# mainboard_v3.net
KiCad netlist of a schematic drawn in EAGLE
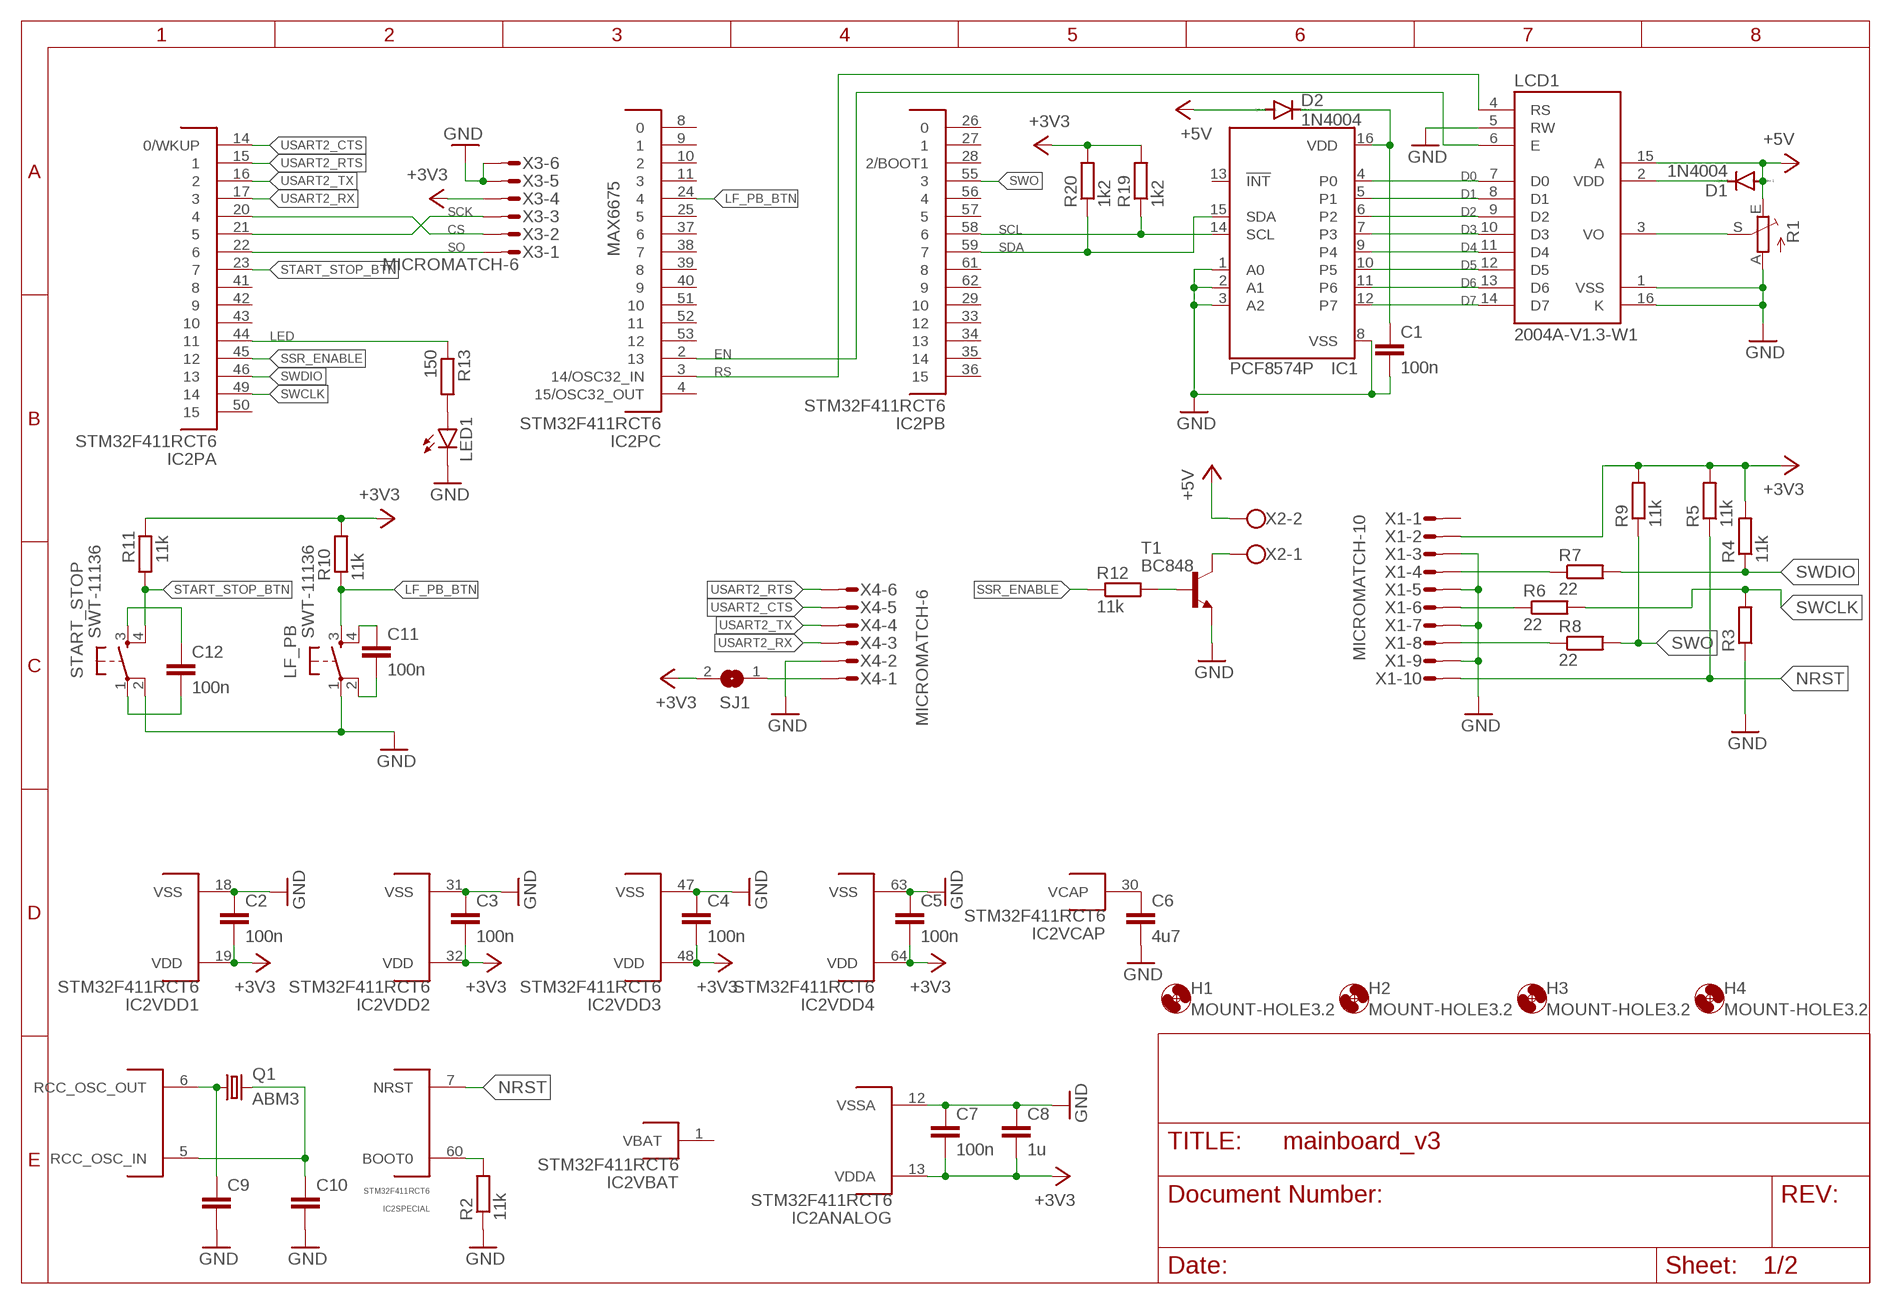
[diagram p0: schematic, sheet 1]
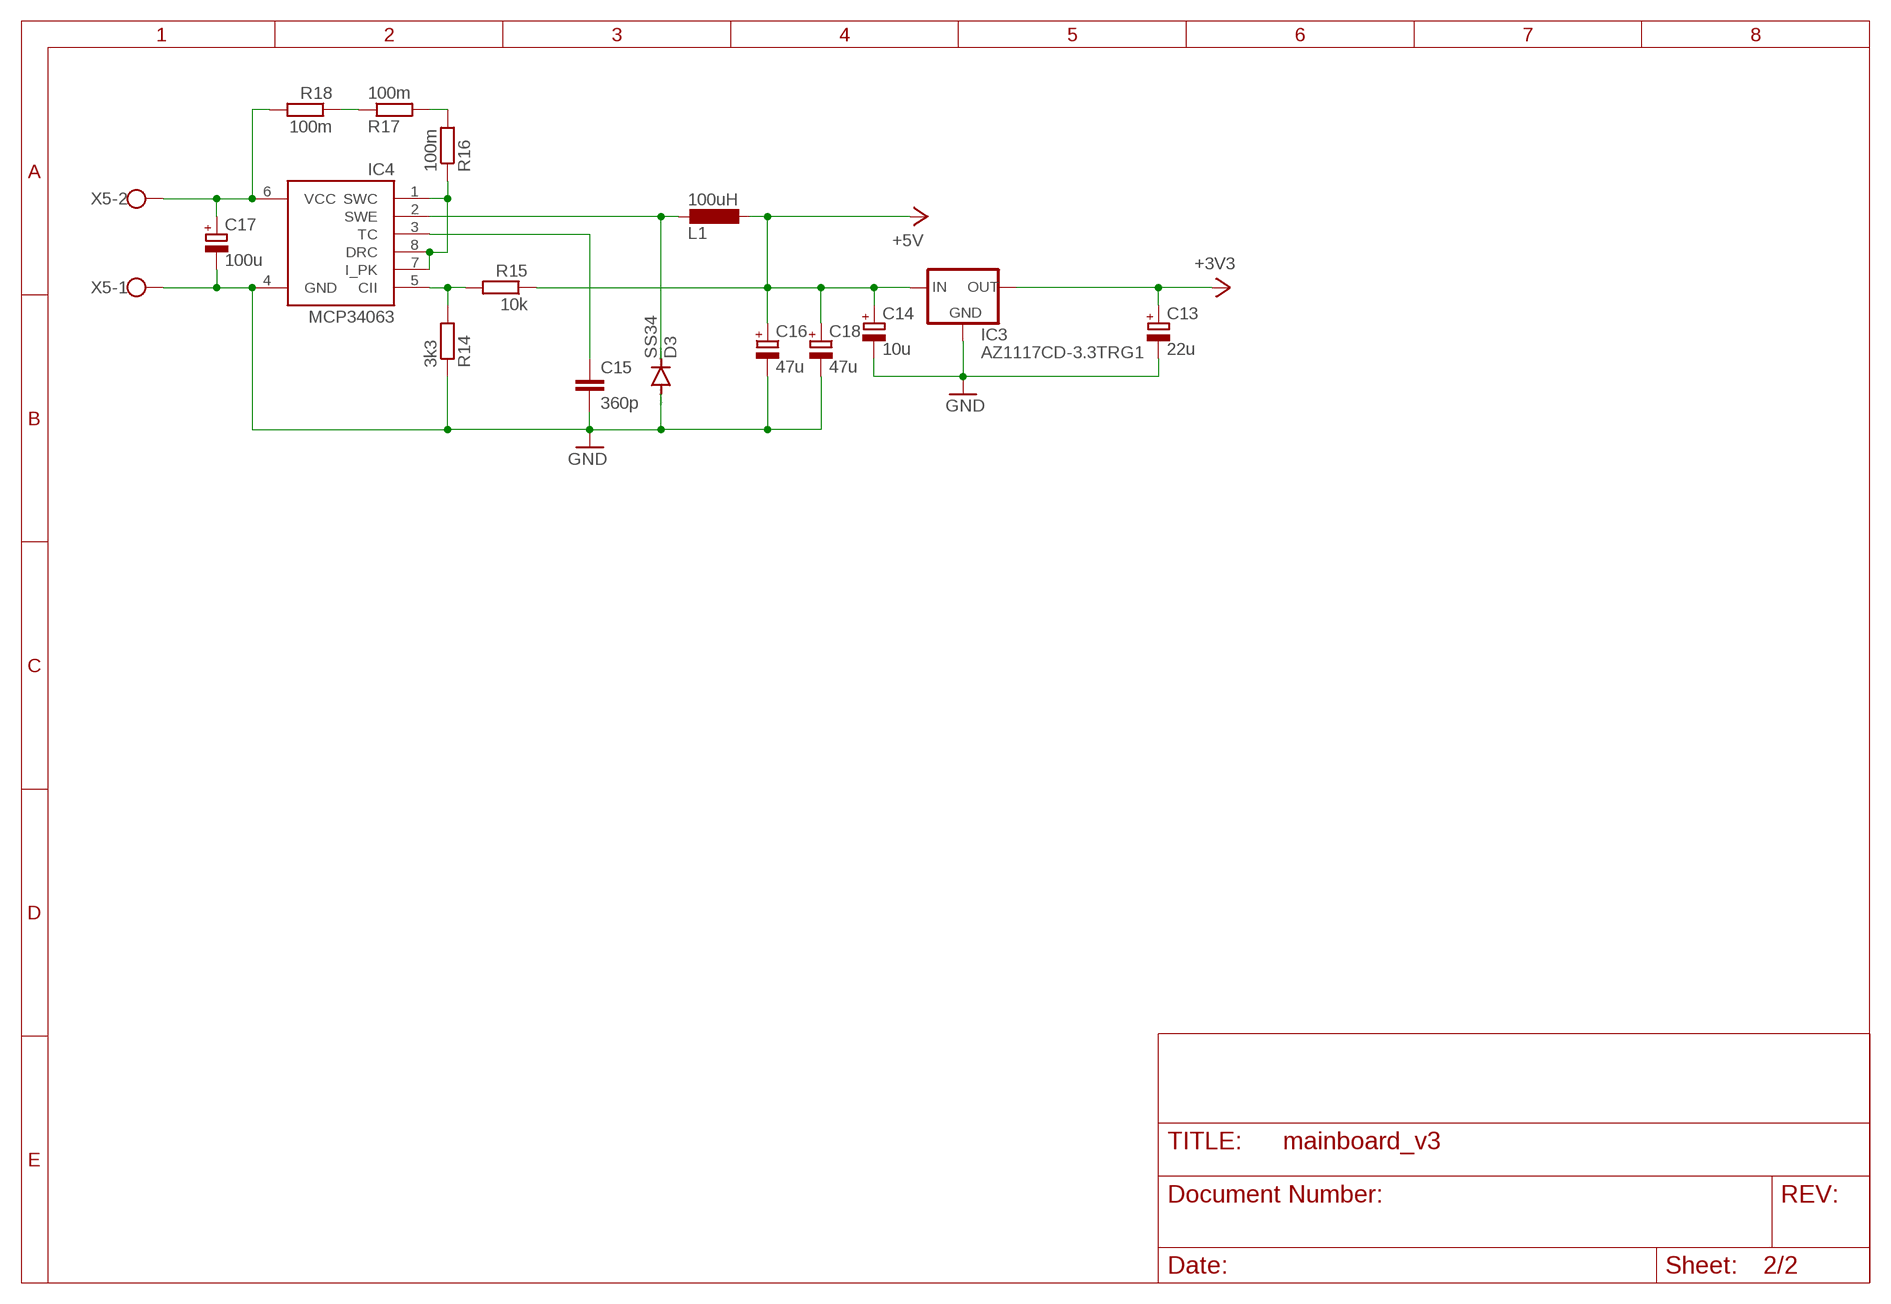
[diagram p1: schematic, sheet 2]

(export (version "E")
  (design (tool "Eeschema 10.0.6"))
  (components
    (comp (ref "C1")
      (value "100n")
      (footprint "eagle-import:C0805")
      (libsource (lib "eagle-import") (part "C-EUC0805"))
    )
    (comp (ref "C2")
      (value "100n")
      (footprint "eagle-import:C0805")
      (libsource (lib "eagle-import") (part "C-EUC0805"))
    )
    (comp (ref "C3")
      (value "100n")
      (footprint "eagle-import:C0805")
      (libsource (lib "eagle-import") (part "C-EUC0805"))
    )
    (comp (ref "C4")
      (value "100n")
      (footprint "eagle-import:C0805")
      (libsource (lib "eagle-import") (part "C-EUC0805"))
    )
    (comp (ref "C5")
      (value "100n")
      (footprint "eagle-import:C0805")
      (libsource (lib "eagle-import") (part "C-EUC0805"))
    )
    (comp (ref "C6")
      (value "4u7")
      (footprint "eagle-import:C0805")
      (libsource (lib "eagle-import") (part "C-EUC0805"))
    )
    (comp (ref "C7")
      (value "100n")
      (footprint "eagle-import:C0805")
      (libsource (lib "eagle-import") (part "C-EUC0805"))
    )
    (comp (ref "C8")
      (value "1u")
      (footprint "eagle-import:C0805")
      (libsource (lib "eagle-import") (part "C-EUC0805"))
    )
    (comp (ref "C9")
      (value "C-EUC0805")
      (footprint "eagle-import:C0805")
      (libsource (lib "eagle-import") (part "C-EUC0805"))
    )
    (comp (ref "C10")
      (value "C-EUC0805")
      (footprint "eagle-import:C0805")
      (libsource (lib "eagle-import") (part "C-EUC0805"))
    )
    (comp (ref "C11")
      (value "100n")
      (footprint "eagle-import:C0805")
      (libsource (lib "eagle-import") (part "C-EUC0805"))
    )
    (comp (ref "C12")
      (value "100n")
      (footprint "eagle-import:C0805")
      (libsource (lib "eagle-import") (part "C-EUC0805"))
    )
    (comp (ref "D1")
      (value "1N4004")
      (footprint "eagle-import:DO41-10")
      (libsource (lib "eagle-import") (part "1N4004"))
    )
    (comp (ref "D2")
      (value "1N4004")
      (footprint "eagle-import:DO41-10")
      (libsource (lib "eagle-import") (part "1N4004"))
    )
    (comp (ref "H1")
      (value "MOUNT-HOLE3.2")
      (footprint "eagle-import:3,2")
      (libsource (lib "eagle-import") (part "MOUNT-HOLE3.2"))
    )
    (comp (ref "H2")
      (value "MOUNT-HOLE3.2")
      (footprint "eagle-import:3,2")
      (libsource (lib "eagle-import") (part "MOUNT-HOLE3.2"))
    )
    (comp (ref "H3")
      (value "MOUNT-HOLE3.2")
      (footprint "eagle-import:3,2")
      (libsource (lib "eagle-import") (part "MOUNT-HOLE3.2"))
    )
    (comp (ref "H4")
      (value "MOUNT-HOLE3.2")
      (footprint "eagle-import:3,2")
      (libsource (lib "eagle-import") (part "MOUNT-HOLE3.2"))
    )
    (comp (ref "IC1")
      (value "PCF8574P")
      (footprint "eagle-import:DIL16")
      (fields (field (name "MPN") "PCF8574PN"))
      (libsource (lib "eagle-import") (part "PCF8574P"))
    )
    (comp (ref "IC2")
      (value "STM32F411RCT6")
      (footprint "eagle-import:QFP50P1200X1200X160-64N")
      (libsource (lib "eagle-import") (part "STM32F411RCT6"))
    )
    (comp (ref "LCD1")
      (value "2004A-V1.3-W1")
      (footprint "eagle-import:2004A-V1.3-W1")
      (libsource (lib "eagle-import") (part "2004A-V1.3-W1"))
    )
    (comp (ref "LED1")
      (value "LED5MM")
      (footprint "eagle-import:LED5MM")
      (libsource (lib "eagle-import") (part "LED5MM"))
    )
    (comp (ref "LF_PB")
      (value "SWT-11136")
      (footprint "eagle-import:SWT-11136")
      (libsource (lib "eagle-import") (part "SWT-11136"))
    )
    (comp (ref "Q1")
      (value "ABM3")
      (footprint "eagle-import:XTALDFN500X320X130-2N")
      (libsource (lib "eagle-import") (part "ABM3"))
    )
    (comp (ref "R1")
      (value "TRIM_EU-CA9V")
      (footprint "eagle-import:CA9V")
      (libsource (lib "eagle-import") (part "TRIM_EU-CA9V"))
    )
    (comp (ref "R2")
      (value "11k")
      (footprint "eagle-import:R1206")
      (libsource (lib "eagle-import") (part "R-EU_R1206"))
    )
    (comp (ref "R3")
      (value "R-EU_R1206")
      (footprint "eagle-import:R1206")
      (libsource (lib "eagle-import") (part "R-EU_R1206"))
    )
    (comp (ref "R4")
      (value "11k")
      (footprint "eagle-import:R1206")
      (libsource (lib "eagle-import") (part "R-EU_R1206"))
    )
    (comp (ref "R5")
      (value "11k")
      (footprint "eagle-import:R1206")
      (libsource (lib "eagle-import") (part "R-EU_R1206"))
    )
    (comp (ref "R6")
      (value "22")
      (footprint "eagle-import:R0603")
      (libsource (lib "eagle-import") (part "R-EU_R0603"))
    )
    (comp (ref "R7")
      (value "22")
      (footprint "eagle-import:R0603")
      (libsource (lib "eagle-import") (part "R-EU_R0603"))
    )
    (comp (ref "R8")
      (value "22")
      (footprint "eagle-import:R0603")
      (libsource (lib "eagle-import") (part "R-EU_R0603"))
    )
    (comp (ref "R9")
      (value "11k")
      (footprint "eagle-import:R1206")
      (libsource (lib "eagle-import") (part "R-EU_R1206"))
    )
    (comp (ref "R10")
      (value "11k")
      (footprint "eagle-import:R1206")
      (libsource (lib "eagle-import") (part "R-EU_R1206"))
    )
    (comp (ref "R11")
      (value "11k")
      (footprint "eagle-import:R1206")
      (libsource (lib "eagle-import") (part "R-EU_R1206"))
    )
    (comp (ref "R12")
      (value "11k")
      (footprint "eagle-import:R1206")
      (libsource (lib "eagle-import") (part "R-EU_R1206"))
    )
    (comp (ref "R13")
      (value "150")
      (footprint "eagle-import:R0805")
      (libsource (lib "eagle-import") (part "R-EU_R0805"))
    )
    (comp (ref "R19")
      (value "1k2")
      (footprint "eagle-import:0207_12")
      (libsource (lib "eagle-import") (part "R-EU_0207/12"))
    )
    (comp (ref "R20")
      (value "1k2")
      (footprint "eagle-import:0207_12")
      (libsource (lib "eagle-import") (part "R-EU_0207/12"))
    )
    (comp (ref "SJ1") (value "SJ") (footprint "eagle-import:SJ") (libsource (lib "eagle-import") (part "SJ")))
    (comp (ref "START_STOP")
      (value "SWT-11136")
      (footprint "eagle-import:SWT-11136")
      (libsource (lib "eagle-import") (part "SWT-11136"))
    )
    (comp (ref "T1")
      (value "BC848")
      (footprint "eagle-import:SOT23")
      (libsource (lib "eagle-import") (part "BC848"))
    )
    (comp (ref "X1")
      (value "MICROMATCH-10")
      (footprint "eagle-import:MICROMATCH-10")
      (fields (field (name "MF") "FARNELL") (field (name "MPN") "8-215464-0"))
      (libsource (lib "eagle-import") (part "MICROMATCH-10"))
    )
    (comp (ref "X2")
      (value "W237-102")
      (footprint "eagle-import:W237-102")
      (fields (field (name "MPN") "237-102"))
      (libsource (lib "eagle-import") (part "W237-102"))
    )
    (comp (ref "X3")
      (value "MICROMATCH-6")
      (footprint "eagle-import:MICROMATCH-6")
      (fields (field (name "MPN") "7-215464-6"))
      (libsource (lib "eagle-import") (part "MICROMATCH-6"))
    )
    (comp (ref "X4")
      (value "MICROMATCH-6")
      (footprint "eagle-import:MICROMATCH-6")
      (fields (field (name "MPN") "7-215464-6"))
      (libsource (lib "eagle-import") (part "MICROMATCH-6"))
    )
    (comp (ref "C13")
      (value "22u")
      (footprint "eagle-import:SMC_B")
      (libsource (lib "eagle-import") (part "CPOL-EUSMCB"))
    )
    (comp (ref "C14")
      (value "10u")
      (footprint "eagle-import:SMC_A")
      (libsource (lib "eagle-import") (part "CPOL-EUSMCA"))
    )
    (comp (ref "C15")
      (value "360p")
      (footprint "eagle-import:C1206")
      (libsource (lib "eagle-import") (part "C-EUC1206"))
    )
    (comp (ref "C16")
      (value "47u")
      (footprint "eagle-import:SMC_D")
      (libsource (lib "eagle-import") (part "CPOL-EUSMCD"))
    )
    (comp (ref "C17")
      (value "100u")
      (footprint "eagle-import:E5-8,5")
      (libsource (lib "eagle-import") (part "CPOL-EUE5-8.5"))
    )
    (comp (ref "C18")
      (value "47u")
      (footprint "eagle-import:SMC_D")
      (libsource (lib "eagle-import") (part "CPOL-EUSMCD"))
    )
    (comp (ref "D3")
      (value "SS34")
      (footprint "eagle-import:SMB")
      (libsource (lib "eagle-import") (part "DIODE-SMB"))
    )
    (comp (ref "IC3")
      (value "AZ1117CD-3.3TRG1")
      (footprint "eagle-import:TO228P1014X240-3N")
      (libsource (lib "eagle-import") (part "AZ1117CD-3.3TRG1"))
    )
    (comp (ref "IC4")
      (value "MCP34063")
      (footprint "eagle-import:SOIC127P600X175-8N")
      (libsource (lib "eagle-import") (part "MCP34063"))
    )
    (comp (ref "L1")
      (value "100uH")
      (footprint "eagle-import:INDM7770X500N")
      (libsource (lib "eagle-import") (part "SOMETHING_100UH"))
    )
    (comp (ref "R14")
      (value "3k3")
      (footprint "eagle-import:R1206")
      (libsource (lib "eagle-import") (part "R-EU_R1206"))
    )
    (comp (ref "R15")
      (value "10k")
      (footprint "eagle-import:R1206")
      (libsource (lib "eagle-import") (part "R-EU_R1206"))
    )
    (comp (ref "R16")
      (value "100m")
      (footprint "eagle-import:0309_12")
      (libsource (lib "eagle-import") (part "R-EU_0309/12"))
    )
    (comp (ref "R17")
      (value "100m")
      (footprint "eagle-import:0309_12")
      (libsource (lib "eagle-import") (part "R-EU_0309/12"))
    )
    (comp (ref "R18")
      (value "100m")
      (footprint "eagle-import:0309_12")
      (libsource (lib "eagle-import") (part "R-EU_0309/12"))
    )
    (comp (ref "X5")
      (value "W237-102")
      (footprint "eagle-import:W237-102")
      (fields (field (name "MPN") "237-102"))
      (libsource (lib "eagle-import") (part "W237-102"))
    )
  )
  (nets
    (net (code "1") (name "+3V3") (class "Default")
      (node (ref "C13") (pin "+") (pinfunction "+_+") (pintype "passive"))
      (node (ref "C2") (pin "2") (pinfunction "2_2") (pintype "passive"))
      (node (ref "C3") (pin "2") (pinfunction "2_2") (pintype "passive"))
      (node (ref "C4") (pin "2") (pinfunction "2_2") (pintype "passive"))
      (node (ref "C5") (pin "2") (pinfunction "2_2") (pintype "passive"))
      (node (ref "C7") (pin "2") (pinfunction "2_2") (pintype "passive"))
      (node (ref "C8") (pin "2") (pinfunction "2_2") (pintype "passive"))
      (node (ref "IC2") (pin "13") (pinfunction "VDDA_13") (pintype "power_in"))
      (node (ref "IC2") (pin "19") (pinfunction "VDD_19") (pintype "power_in"))
      (node (ref "IC2") (pin "32") (pinfunction "VDD_32") (pintype "power_in"))
      (node (ref "IC2") (pin "48") (pinfunction "VDD_48") (pintype "power_in"))
      (node (ref "IC2") (pin "64") (pinfunction "VDD_64") (pintype "power_in"))
      (node (ref "IC3") (pin "3") (pinfunction "OUT_3") (pintype "passive"))
      (node (ref "R10") (pin "2") (pinfunction "2_2") (pintype "passive"))
      (node (ref "R11") (pin "2") (pinfunction "2_2") (pintype "passive"))
      (node (ref "R19") (pin "2") (pinfunction "2_2") (pintype "passive"))
      (node (ref "R20") (pin "2") (pinfunction "2_2") (pintype "passive"))
      (node (ref "R4") (pin "2") (pinfunction "2_2") (pintype "passive"))
      (node (ref "R5") (pin "2") (pinfunction "2_2") (pintype "passive"))
      (node (ref "R9") (pin "2") (pinfunction "2_2") (pintype "passive"))
      (node (ref "SJ1") (pin "2") (pinfunction "2_2") (pintype "passive"))
      (node (ref "X1") (pin "2") (pinfunction "S_2") (pintype "passive"))
      (node (ref "X3") (pin "4") (pinfunction "S_4") (pintype "passive"))
    )
    (net (code "2") (name "+5V") (class "Default")
      (node (ref "C14") (pin "+") (pinfunction "+_+") (pintype "passive"))
      (node (ref "C16") (pin "+") (pinfunction "+_+") (pintype "passive"))
      (node (ref "C18") (pin "+") (pinfunction "+_+") (pintype "passive"))
      (node (ref "D1") (pin "A") (pinfunction "A_A") (pintype "passive"))
      (node (ref "D2") (pin "A") (pinfunction "A_A") (pintype "passive"))
      (node (ref "IC3") (pin "2") (pinfunction "IN_2") (pintype "input"))
      (node (ref "L1") (pin "1") (pinfunction "1_1") (pintype "passive"))
      (node (ref "LCD1") (pin "15") (pinfunction "A_15") (pintype "power_in"))
      (node (ref "R1") (pin "E") (pinfunction "E_E") (pintype "passive"))
      (node (ref "R15") (pin "1") (pinfunction "1_1") (pintype "passive"))
      (node (ref "X2") (pin "2") (pinfunction "KL_2") (pintype "passive"))
    )
    (net (code "3") (name "CS") (class "Default")
      (node (ref "IC2") (pin "20") (pinfunction "4_20") (pintype "bidirectional"))
      (node (ref "X3") (pin "2") (pinfunction "S_2") (pintype "passive"))
    )
    (net (code "4") (name "D0") (class "Default")
      (node (ref "IC1") (pin "4") (pinfunction "P0_4") (pintype "bidirectional"))
      (node (ref "LCD1") (pin "7") (pinfunction "D0_7") (pintype "bidirectional"))
    )
    (net (code "5") (name "D1") (class "Default")
      (node (ref "IC1") (pin "5") (pinfunction "P1_5") (pintype "bidirectional"))
      (node (ref "LCD1") (pin "8") (pinfunction "D1_8") (pintype "bidirectional"))
    )
    (net (code "6") (name "D2") (class "Default")
      (node (ref "IC1") (pin "6") (pinfunction "P2_6") (pintype "bidirectional"))
      (node (ref "LCD1") (pin "9") (pinfunction "D2_9") (pintype "bidirectional"))
    )
    (net (code "7") (name "D3") (class "Default")
      (node (ref "IC1") (pin "7") (pinfunction "P3_7") (pintype "bidirectional"))
      (node (ref "LCD1") (pin "10") (pinfunction "D3_10") (pintype "bidirectional"))
    )
    (net (code "8") (name "D4") (class "Default")
      (node (ref "IC1") (pin "9") (pinfunction "P4_9") (pintype "bidirectional"))
      (node (ref "LCD1") (pin "11") (pinfunction "D4_11") (pintype "bidirectional"))
    )
    (net (code "9") (name "D5") (class "Default")
      (node (ref "IC1") (pin "10") (pinfunction "P5_10") (pintype "bidirectional"))
      (node (ref "LCD1") (pin "12") (pinfunction "D5_12") (pintype "bidirectional"))
    )
    (net (code "10") (name "D6") (class "Default")
      (node (ref "IC1") (pin "11") (pinfunction "P6_11") (pintype "bidirectional"))
      (node (ref "LCD1") (pin "13") (pinfunction "D6_13") (pintype "bidirectional"))
    )
    (net (code "11") (name "D7") (class "Default")
      (node (ref "IC1") (pin "12") (pinfunction "P7_12") (pintype "bidirectional"))
      (node (ref "LCD1") (pin "14") (pinfunction "D7_14") (pintype "bidirectional"))
    )
    (net (code "12") (name "EN") (class "Default")
      (node (ref "IC2") (pin "2") (pinfunction "13_2") (pintype "bidirectional"))
      (node (ref "LCD1") (pin "6") (pinfunction "E_6") (pintype "input"))
    )
    (net (code "13") (name "GND") (class "Default")
      (node (ref "C1") (pin "2") (pinfunction "2_2") (pintype "passive"))
      (node (ref "C10") (pin "2") (pinfunction "2_2") (pintype "passive"))
      (node (ref "C13") (pin "-") (pinfunction "-_-") (pintype "passive"))
      (node (ref "C14") (pin "-") (pinfunction "-_-") (pintype "passive"))
      (node (ref "C15") (pin "2") (pinfunction "2_2") (pintype "passive"))
      (node (ref "C16") (pin "-") (pinfunction "-_-") (pintype "passive"))
      (node (ref "C17") (pin "-") (pinfunction "-_-") (pintype "passive"))
      (node (ref "C18") (pin "-") (pinfunction "-_-") (pintype "passive"))
      (node (ref "C2") (pin "1") (pinfunction "1_1") (pintype "passive"))
      (node (ref "C3") (pin "1") (pinfunction "1_1") (pintype "passive"))
      (node (ref "C4") (pin "1") (pinfunction "1_1") (pintype "passive"))
      (node (ref "C5") (pin "1") (pinfunction "1_1") (pintype "passive"))
      (node (ref "C6") (pin "2") (pinfunction "2_2") (pintype "passive"))
      (node (ref "C7") (pin "1") (pinfunction "1_1") (pintype "passive"))
      (node (ref "C8") (pin "1") (pinfunction "1_1") (pintype "passive"))
      (node (ref "C9") (pin "2") (pinfunction "2_2") (pintype "passive"))
      (node (ref "D3") (pin "A") (pinfunction "A_A") (pintype "passive"))
      (node (ref "IC1") (pin "1") (pinfunction "A0_1") (pintype "input"))
      (node (ref "IC1") (pin "2") (pinfunction "A1_2") (pintype "input"))
      (node (ref "IC1") (pin "3") (pinfunction "A2_3") (pintype "input"))
      (node (ref "IC1") (pin "8") (pinfunction "VSS_8") (pintype "power_in"))
      (node (ref "IC2") (pin "12") (pinfunction "VSSA_12") (pintype "power_in"))
      (node (ref "IC2") (pin "18") (pinfunction "VSS_18") (pintype "power_in"))
      (node (ref "IC2") (pin "31") (pinfunction "VSS_31") (pintype "power_in"))
      (node (ref "IC2") (pin "47") (pinfunction "VSS_47") (pintype "power_in"))
      (node (ref "IC2") (pin "63") (pinfunction "VSS_63") (pintype "power_in"))
      (node (ref "IC3") (pin "1") (pinfunction "GND_1") (pintype "input"))
      (node (ref "IC4") (pin "4") (pinfunction "GND_4") (pintype "power_in"))
      (node (ref "LCD1") (pin "1") (pinfunction "VSS_1") (pintype "power_in"))
      (node (ref "LCD1") (pin "16") (pinfunction "K_16") (pintype "power_in"))
      (node (ref "LCD1") (pin "5") (pinfunction "RW_5") (pintype "input"))
      (node (ref "LED1") (pin "K") (pinfunction "C_K") (pintype "passive"))
      (node (ref "LF_PB") (pin "1") (pinfunction "P_1") (pintype "passive"))
      (node (ref "R1") (pin "A") (pinfunction "A_A") (pintype "passive"))
      (node (ref "R14") (pin "1") (pinfunction "1_1") (pintype "passive"))
      (node (ref "R2") (pin "1") (pinfunction "1_1") (pintype "passive"))
      (node (ref "R3") (pin "1") (pinfunction "1_1") (pintype "passive"))
      (node (ref "START_STOP") (pin "2") (pinfunction "P1_2") (pintype "passive"))
      (node (ref "T1") (pin "2") (pinfunction "E_2") (pintype "passive"))
      (node (ref "X1") (pin "3") (pinfunction "S_3") (pintype "passive"))
      (node (ref "X1") (pin "5") (pinfunction "S_5") (pintype "passive"))
      (node (ref "X1") (pin "7") (pinfunction "S_7") (pintype "passive"))
      (node (ref "X1") (pin "9") (pinfunction "S_9") (pintype "passive"))
      (node (ref "X3") (pin "5") (pinfunction "S_5") (pintype "passive"))
      (node (ref "X3") (pin "6") (pinfunction "S_6") (pintype "passive"))
      (node (ref "X4") (pin "2") (pinfunction "S_2") (pintype "passive"))
      (node (ref "X5") (pin "1") (pinfunction "KL_1") (pintype "passive"))
    )
    (net (code "14") (name "LED") (class "Default")
      (node (ref "IC2") (pin "44") (pinfunction "11_44") (pintype "bidirectional"))
      (node (ref "R13") (pin "1") (pinfunction "1_1") (pintype "passive"))
    )
    (net (code "15") (name "LF_PB_BTN") (class "Default")
      (node (ref "IC2") (pin "24") (pinfunction "4_24") (pintype "bidirectional"))
      (node (ref "LF_PB") (pin "3") (pinfunction "S_3") (pintype "passive"))
      (node (ref "R10") (pin "1") (pinfunction "1_1") (pintype "passive"))
    )
    (net (code "16") (name "NRST") (class "Default")
      (node (ref "IC2") (pin "7") (pinfunction "NRST_7") (pintype "bidirectional"))
      (node (ref "R5") (pin "1") (pinfunction "1_1") (pintype "passive"))
      (node (ref "X1") (pin "10") (pinfunction "S_10") (pintype "passive"))
    )
    (net (code "17") (name "Net-(IC1-VDD)") (class "Default")
      (node (ref "C1") (pin "1") (pinfunction "1_1") (pintype "passive"))
      (node (ref "D2") (pin "C") (pinfunction "C_C") (pintype "passive"))
      (node (ref "IC1") (pin "16") (pinfunction "VDD_16") (pintype "power_in"))
    )
    (net (code "18") (name "Net-(IC2F-BOOT0)") (class "Default")
      (node (ref "IC2") (pin "60") (pinfunction "BOOT0_60") (pintype "bidirectional"))
      (node (ref "R2") (pin "2") (pinfunction "2_2") (pintype "passive"))
    )
    (net (code "19") (name "Net-(IC2F-RCC_OSC_IN)") (class "Default")
      (node (ref "C10") (pin "1") (pinfunction "1_1") (pintype "passive"))
      (node (ref "IC2") (pin "5") (pinfunction "RCC_OSC_IN_5") (pintype "bidirectional"))
      (node (ref "Q1") (pin "2") (pinfunction "2_2") (pintype "passive"))
    )
    (net (code "20") (name "Net-(IC2F-RCC_OSC_OUT)") (class "Default")
      (node (ref "C9") (pin "1") (pinfunction "1_1") (pintype "passive"))
      (node (ref "IC2") (pin "6") (pinfunction "RCC_OSC_OUT_6") (pintype "bidirectional"))
      (node (ref "Q1") (pin "1") (pinfunction "1_1") (pintype "passive"))
    )
    (net (code "21") (name "Net-(IC2H-VCAP)") (class "Default")
      (node (ref "C6") (pin "1") (pinfunction "1_1") (pintype "passive"))
      (node (ref "IC2") (pin "30") (pinfunction "VCAP_30") (pintype "passive"))
    )
    (net (code "22") (name "Net-(IC4-CII)") (class "Default")
      (node (ref "IC4") (pin "5") (pinfunction "CII_5") (pintype "bidirectional"))
      (node (ref "R14") (pin "2") (pinfunction "2_2") (pintype "passive"))
      (node (ref "R15") (pin "2") (pinfunction "2_2") (pintype "passive"))
    )
    (net (code "23") (name "Net-(IC4-DRC)") (class "Default")
      (node (ref "IC4") (pin "1") (pinfunction "SWC_1") (pintype "bidirectional"))
      (node (ref "IC4") (pin "7") (pinfunction "I_PK_7") (pintype "bidirectional"))
      (node (ref "IC4") (pin "8") (pinfunction "DRC_8") (pintype "bidirectional"))
      (node (ref "R16") (pin "1") (pinfunction "1_1") (pintype "passive"))
    )
    (net (code "24") (name "Net-(IC4-SWE)") (class "Default")
      (node (ref "D3") (pin "C") (pinfunction "C_C") (pintype "passive"))
      (node (ref "IC4") (pin "2") (pinfunction "SWE_2") (pintype "bidirectional"))
      (node (ref "L1") (pin "2") (pinfunction "2_2") (pintype "passive"))
    )
    (net (code "25") (name "Net-(IC4-TC)") (class "Default")
      (node (ref "C15") (pin "1") (pinfunction "1_1") (pintype "passive"))
      (node (ref "IC4") (pin "3") (pinfunction "TC_3") (pintype "bidirectional"))
    )
    (net (code "26") (name "Net-(IC4-VCC)") (class "Default")
      (node (ref "C17") (pin "+") (pinfunction "+_+") (pintype "passive"))
      (node (ref "IC4") (pin "6") (pinfunction "VCC_6") (pintype "power_in"))
      (node (ref "R18") (pin "2") (pinfunction "2_2") (pintype "passive"))
      (node (ref "X5") (pin "2") (pinfunction "KL_2") (pintype "passive"))
    )
    (net (code "27") (name "Net-(LCD1-VDD)") (class "Default")
      (node (ref "D1") (pin "C") (pinfunction "C_C") (pintype "passive"))
      (node (ref "LCD1") (pin "2") (pinfunction "VDD_2") (pintype "power_in"))
    )
    (net (code "28") (name "Net-(LCD1-VO)") (class "Default")
      (node (ref "LCD1") (pin "3") (pinfunction "VO_3") (pintype "power_in"))
      (node (ref "R1") (pin "S") (pinfunction "S_S") (pintype "passive"))
    )
    (net (code "29") (name "Net-(LED1-PadA)") (class "Default")
      (node (ref "LED1") (pin "A") (pinfunction "A_A") (pintype "passive"))
      (node (ref "R13") (pin "2") (pinfunction "2_2") (pintype "passive"))
    )
    (net (code "30") (name "Net-(LF_PB-P1)") (class "Default")
      (node (ref "C11") (pin "2") (pinfunction "2_2") (pintype "passive"))
      (node (ref "LF_PB") (pin "2") (pinfunction "P1_2") (pintype "passive"))
    )
    (net (code "31") (name "Net-(LF_PB-S1)") (class "Default")
      (node (ref "C11") (pin "1") (pinfunction "1_1") (pintype "passive"))
      (node (ref "LF_PB") (pin "4") (pinfunction "S1_4") (pintype "passive"))
    )
    (net (code "32") (name "Net-(R16-Pad2)") (class "Default")
      (node (ref "R16") (pin "2") (pinfunction "2_2") (pintype "passive"))
      (node (ref "R17") (pin "2") (pinfunction "2_2") (pintype "passive"))
    )
    (net (code "33") (name "Net-(R17-Pad1)") (class "Default")
      (node (ref "R17") (pin "1") (pinfunction "1_1") (pintype "passive"))
      (node (ref "R18") (pin "1") (pinfunction "1_1") (pintype "passive"))
    )
    (net (code "34") (name "Net-(START_STOP-P)") (class "Default")
      (node (ref "C12") (pin "2") (pinfunction "2_2") (pintype "passive"))
      (node (ref "START_STOP") (pin "1") (pinfunction "P_1") (pintype "passive"))
    )
    (net (code "35") (name "Net-(START_STOP-S)") (class "Default")
      (node (ref "C12") (pin "1") (pinfunction "1_1") (pintype "passive"))
      (node (ref "START_STOP") (pin "3") (pinfunction "S_3") (pintype "passive"))
    )
    (net (code "36") (name "Net-(T1-B)") (class "Default")
      (node (ref "R12") (pin "2") (pinfunction "2_2") (pintype "passive"))
      (node (ref "T1") (pin "1") (pinfunction "B_1") (pintype "passive"))
    )
    (net (code "37") (name "Net-(T1-C)") (class "Default")
      (node (ref "T1") (pin "3") (pinfunction "C_3") (pintype "passive"))
      (node (ref "X2") (pin "1") (pinfunction "KL_1") (pintype "passive"))
    )
    (net (code "38") (name "Net-(X1E-S)") (class "Default")
      (node (ref "R7") (pin "1") (pinfunction "1_1") (pintype "passive"))
      (node (ref "X1") (pin "4") (pinfunction "S_4") (pintype "passive"))
    )
    (net (code "39") (name "Net-(X1G-S)") (class "Default")
      (node (ref "R6") (pin "1") (pinfunction "1_1") (pintype "passive"))
      (node (ref "X1") (pin "6") (pinfunction "S_6") (pintype "passive"))
    )
    (net (code "40") (name "Net-(X1I-S)") (class "Default")
      (node (ref "R8") (pin "1") (pinfunction "1_1") (pintype "passive"))
      (node (ref "X1") (pin "8") (pinfunction "S_8") (pintype "passive"))
    )
    (net (code "41") (name "Net-(X4A-S)") (class "Default")
      (node (ref "SJ1") (pin "1") (pinfunction "1_1") (pintype "passive"))
      (node (ref "X4") (pin "1") (pinfunction "S_1") (pintype "passive"))
    )
    (net (code "42") (name "RS") (class "Default")
      (node (ref "IC2") (pin "3") (pinfunction "14/OSC32_IN_3") (pintype "bidirectional"))
      (node (ref "LCD1") (pin "4") (pinfunction "RS_4") (pintype "input"))
    )
    (net (code "43") (name "SCK") (class "Default")
      (node (ref "IC2") (pin "21") (pinfunction "5_21") (pintype "bidirectional"))
      (node (ref "X3") (pin "3") (pinfunction "S_3") (pintype "passive"))
    )
    (net (code "44") (name "SCL") (class "Default")
      (node (ref "IC1") (pin "14") (pinfunction "SCL_14") (pintype "input"))
      (node (ref "IC2") (pin "58") (pinfunction "6_58") (pintype "bidirectional"))
      (node (ref "R19") (pin "1") (pinfunction "1_1") (pintype "passive"))
    )
    (net (code "45") (name "SDA") (class "Default")
      (node (ref "IC1") (pin "15") (pinfunction "SDA_15") (pintype "bidirectional"))
      (node (ref "IC2") (pin "59") (pinfunction "7_59") (pintype "bidirectional"))
      (node (ref "R20") (pin "1") (pinfunction "1_1") (pintype "passive"))
    )
    (net (code "46") (name "SO") (class "Default")
      (node (ref "IC2") (pin "22") (pinfunction "6_22") (pintype "bidirectional"))
      (node (ref "X3") (pin "1") (pinfunction "S_1") (pintype "passive"))
    )
    (net (code "47") (name "SSR_ENABLE") (class "Default")
      (node (ref "IC2") (pin "45") (pinfunction "12_45") (pintype "bidirectional"))
      (node (ref "R12") (pin "1") (pinfunction "1_1") (pintype "passive"))
    )
    (net (code "48") (name "START_STOP_BTN") (class "Default")
      (node (ref "IC2") (pin "23") (pinfunction "7_23") (pintype "bidirectional"))
      (node (ref "R11") (pin "1") (pinfunction "1_1") (pintype "passive"))
      (node (ref "START_STOP") (pin "4") (pinfunction "S1_4") (pintype "passive"))
    )
    (net (code "49") (name "SWCLK") (class "Default")
      (node (ref "IC2") (pin "49") (pinfunction "14_49") (pintype "bidirectional"))
      (node (ref "R3") (pin "2") (pinfunction "2_2") (pintype "passive"))
      (node (ref "R6") (pin "2") (pinfunction "2_2") (pintype "passive"))
    )
    (net (code "50") (name "SWDIO") (class "Default")
      (node (ref "IC2") (pin "46") (pinfunction "13_46") (pintype "bidirectional"))
      (node (ref "R4") (pin "1") (pinfunction "1_1") (pintype "passive"))
      (node (ref "R7") (pin "2") (pinfunction "2_2") (pintype "passive"))
    )
    (net (code "51") (name "SWO") (class "Default")
      (node (ref "IC2") (pin "55") (pinfunction "3_55") (pintype "bidirectional"))
      (node (ref "R8") (pin "2") (pinfunction "2_2") (pintype "passive"))
      (node (ref "R9") (pin "1") (pinfunction "1_1") (pintype "passive"))
    )
    (net (code "52") (name "USART2_CTS") (class "Default")
      (node (ref "IC2") (pin "14") (pinfunction "0/WKUP_14") (pintype "bidirectional"))
      (node (ref "X4") (pin "5") (pinfunction "S_5") (pintype "passive"))
    )
    (net (code "53") (name "USART2_RTS") (class "Default")
      (node (ref "IC2") (pin "15") (pinfunction "1_15") (pintype "bidirectional"))
      (node (ref "X4") (pin "6") (pinfunction "S_6") (pintype "passive"))
    )
    (net (code "54") (name "USART2_RX") (class "Default")
      (node (ref "IC2") (pin "17") (pinfunction "3_17") (pintype "bidirectional"))
      (node (ref "X4") (pin "3") (pinfunction "S_3") (pintype "passive"))
    )
    (net (code "55") (name "USART2_TX") (class "Default")
      (node (ref "IC2") (pin "16") (pinfunction "2_16") (pintype "bidirectional"))
      (node (ref "X4") (pin "4") (pinfunction "S_4") (pintype "passive"))
    )
    (net (code "56") (name "VBAT") (class "Default")
      (node (ref "IC2") (pin "1") (pinfunction "VBAT_1") (pintype "power_in"))
    )
    (net (code "57") (name "unconnected-(IC1-~{INT}-Pad13)") (class "Default")
      (node (ref "IC1") (pin "13") (pinfunction "~{INT}_13") (pintype "output"))
    )
    (net (code "58") (name "unconnected-(IC2B-8-Pad41)") (class "Default")
      (node (ref "IC2") (pin "41") (pinfunction "8_41") (pintype "bidirectional"))
    )
    (net (code "59") (name "unconnected-(IC2B-9-Pad42)") (class "Default")
      (node (ref "IC2") (pin "42") (pinfunction "9_42") (pintype "bidirectional"))
    )
    (net (code "60") (name "unconnected-(IC2B-10-Pad43)") (class "Default")
      (node (ref "IC2") (pin "43") (pinfunction "10_43") (pintype "bidirectional"))
    )
    (net (code "61") (name "unconnected-(IC2B-15-Pad50)") (class "Default")
      (node (ref "IC2") (pin "50") (pinfunction "15_50") (pintype "bidirectional"))
    )
    (net (code "62") (name "unconnected-(IC2C-0-Pad26)") (class "Default")
      (node (ref "IC2") (pin "26") (pinfunction "0_26") (pintype "bidirectional"))
    )
    (net (code "63") (name "unconnected-(IC2C-1-Pad27)") (class "Default")
      (node (ref "IC2") (pin "27") (pinfunction "1_27") (pintype "bidirectional"))
    )
    (net (code "64") (name "unconnected-(IC2C-2{slash}BOOT1-Pad28)") (class "Default")
      (node (ref "IC2") (pin "28") (pinfunction "2/BOOT1_28") (pintype "bidirectional"))
    )
    (net (code "65") (name "unconnected-(IC2C-4-Pad56)") (class "Default")
      (node (ref "IC2") (pin "56") (pinfunction "4_56") (pintype "bidirectional"))
    )
    (net (code "66") (name "unconnected-(IC2C-5-Pad57)") (class "Default")
      (node (ref "IC2") (pin "57") (pinfunction "5_57") (pintype "bidirectional"))
    )
    (net (code "67") (name "unconnected-(IC2C-8-Pad61)") (class "Default")
      (node (ref "IC2") (pin "61") (pinfunction "8_61") (pintype "bidirectional"))
    )
    (net (code "68") (name "unconnected-(IC2C-9-Pad62)") (class "Default")
      (node (ref "IC2") (pin "62") (pinfunction "9_62") (pintype "bidirectional"))
    )
    (net (code "69") (name "unconnected-(IC2C-10-Pad29)") (class "Default")
      (node (ref "IC2") (pin "29") (pinfunction "10_29") (pintype "bidirectional"))
    )
    (net (code "70") (name "unconnected-(IC2C-12-Pad33)") (class "Default")
      (node (ref "IC2") (pin "33") (pinfunction "12_33") (pintype "bidirectional"))
    )
    (net (code "71") (name "unconnected-(IC2C-13-Pad34)") (class "Default")
      (node (ref "IC2") (pin "34") (pinfunction "13_34") (pintype "bidirectional"))
    )
    (net (code "72") (name "unconnected-(IC2C-14-Pad35)") (class "Default")
      (node (ref "IC2") (pin "35") (pinfunction "14_35") (pintype "bidirectional"))
    )
    (net (code "73") (name "unconnected-(IC2C-15-Pad36)") (class "Default")
      (node (ref "IC2") (pin "36") (pinfunction "15_36") (pintype "bidirectional"))
    )
    (net (code "74") (name "unconnected-(IC2D-0-Pad8)") (class "Default")
      (node (ref "IC2") (pin "8") (pinfunction "0_8") (pintype "bidirectional"))
    )
    (net (code "75") (name "unconnected-(IC2D-1-Pad9)") (class "Default")
      (node (ref "IC2") (pin "9") (pinfunction "1_9") (pintype "bidirectional"))
    )
    (net (code "76") (name "unconnected-(IC2D-2-Pad10)") (class "Default")
      (node (ref "IC2") (pin "10") (pinfunction "2_10") (pintype "bidirectional"))
    )
    (net (code "77") (name "unconnected-(IC2D-3-Pad11)") (class "Default")
      (node (ref "IC2") (pin "11") (pinfunction "3_11") (pintype "bidirectional"))
    )
    (net (code "78") (name "unconnected-(IC2D-5-Pad25)") (class "Default")
      (node (ref "IC2") (pin "25") (pinfunction "5_25") (pintype "bidirectional"))
    )
    (net (code "79") (name "unconnected-(IC2D-6-Pad37)") (class "Default")
      (node (ref "IC2") (pin "37") (pinfunction "6_37") (pintype "bidirectional"))
    )
    (net (code "80") (name "unconnected-(IC2D-7-Pad38)") (class "Default")
      (node (ref "IC2") (pin "38") (pinfunction "7_38") (pintype "bidirectional"))
    )
    (net (code "81") (name "unconnected-(IC2D-8-Pad39)") (class "Default")
      (node (ref "IC2") (pin "39") (pinfunction "8_39") (pintype "bidirectional"))
    )
    (net (code "82") (name "unconnected-(IC2D-9-Pad40)") (class "Default")
      (node (ref "IC2") (pin "40") (pinfunction "9_40") (pintype "bidirectional"))
    )
    (net (code "83") (name "unconnected-(IC2D-10-Pad51)") (class "Default")
      (node (ref "IC2") (pin "51") (pinfunction "10_51") (pintype "bidirectional"))
    )
    (net (code "84") (name "unconnected-(IC2D-11-Pad52)") (class "Default")
      (node (ref "IC2") (pin "52") (pinfunction "11_52") (pintype "bidirectional"))
    )
    (net (code "85") (name "unconnected-(IC2D-12-Pad53)") (class "Default")
      (node (ref "IC2") (pin "53") (pinfunction "12_53") (pintype "bidirectional"))
    )
    (net (code "86") (name "unconnected-(IC2D-15{slash}OSC32_OUT-Pad4)") (class "Default")
      (node (ref "IC2") (pin "4") (pinfunction "15/OSC32_OUT_4") (pintype "bidirectional"))
    )
    (net (code "87") (name "unconnected-(X1A-S-Pad1)") (class "Default")
      (node (ref "X1") (pin "1") (pinfunction "S_1") (pintype "passive"))
    )
  )
)
